# GoPros.net
KiCad netlist of a schematic drawn in Altium Designer
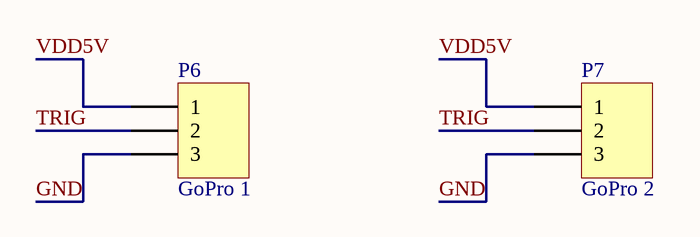
[diagram p0: GoPros.SchDoc]

(export (version "E")
  (design (tool "Eeschema 10.0.6"))
  (components
    (comp (ref "P6")
      (value "GoPro 1")
      (footprint "HDR1X3")
      (description "Header, 3-Pin")
      (fields (field (name "PUBLISHER") "Altium Limited"))
      (libsource (lib "Miscellaneous Connectors") (part "Header 3"))
    )
    (comp (ref "P7")
      (value "GoPro 2")
      (footprint "HDR1X3")
      (description "Header, 3-Pin")
      (fields (field (name "PUBLISHER") "Altium Limited"))
      (libsource (lib "Miscellaneous Connectors") (part "Header 3"))
    )
  )
  (nets
    (net (code "1") (name "/GND") (class "Default")
      (node (ref "P6") (pin "3") (pinfunction "3_3") (pintype "passive"))
      (node (ref "P7") (pin "3") (pinfunction "3_3") (pintype "passive"))
    )
    (net (code "2") (name "/TRIG") (class "Default")
      (node (ref "P6") (pin "2") (pinfunction "2_2") (pintype "passive"))
      (node (ref "P7") (pin "2") (pinfunction "2_2") (pintype "passive"))
    )
    (net (code "3") (name "/VDD5V") (class "Default")
      (node (ref "P6") (pin "1") (pinfunction "1_1") (pintype "passive"))
      (node (ref "P7") (pin "1") (pinfunction "1_1") (pintype "passive"))
    )
  )
)
